# Sheet2_2.net
KiCad netlist of a schematic drawn in Altium Designer
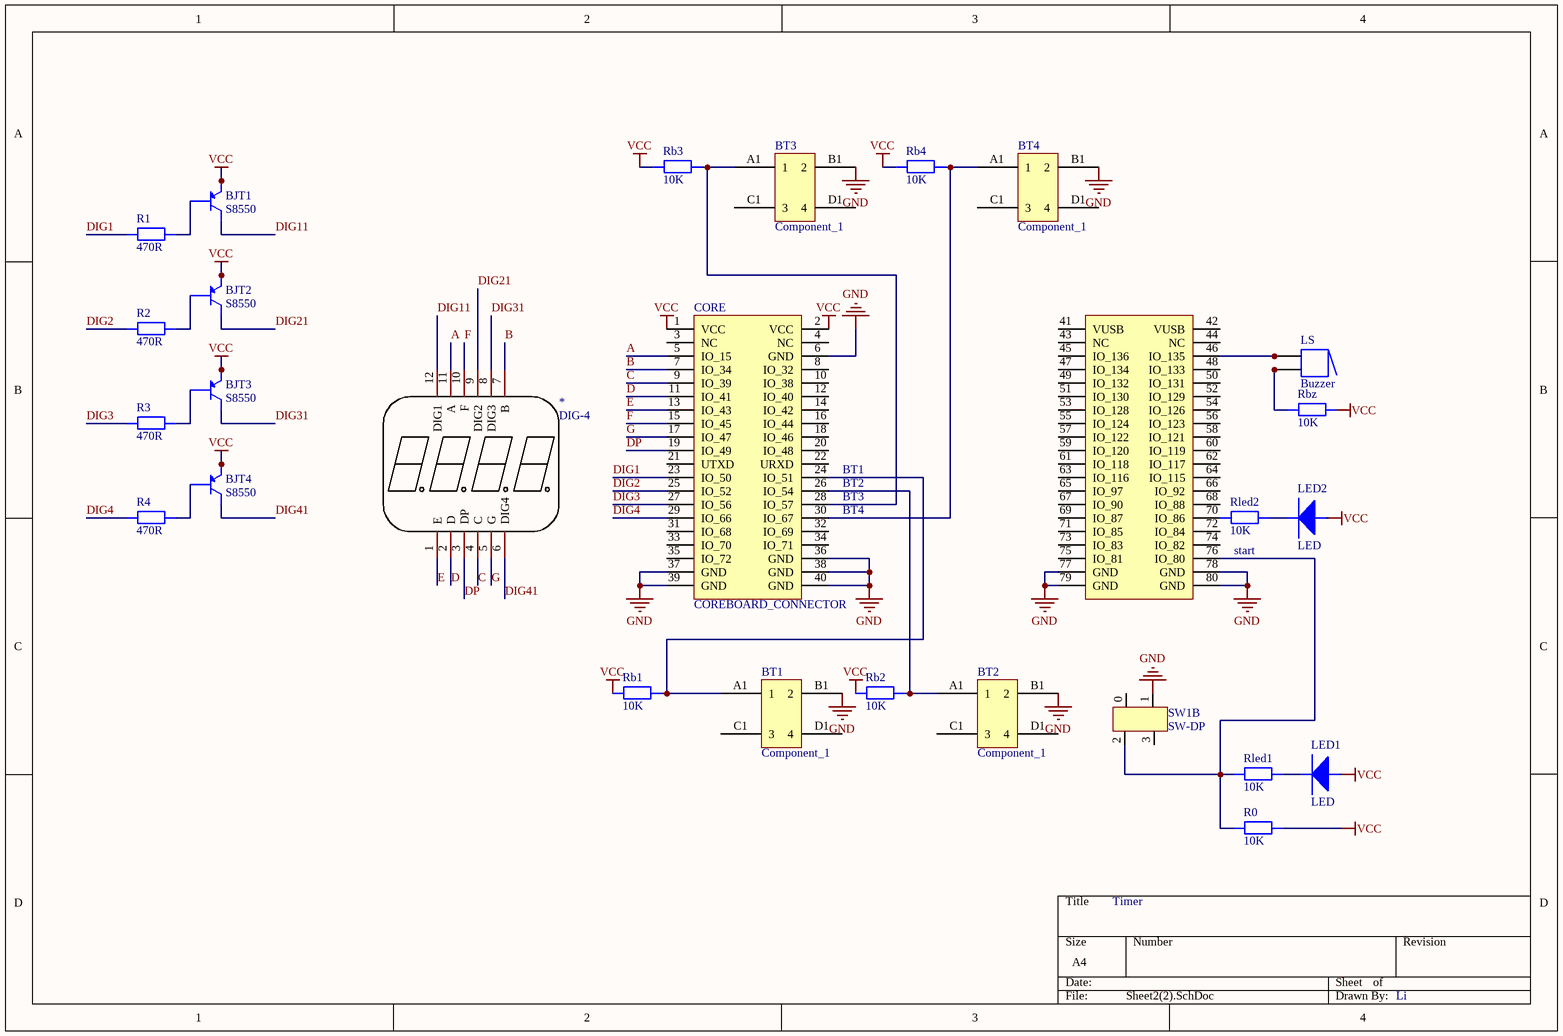
[diagram p0: Sheet2(2).SchDoc]

(export (version "E")
  (design (tool "Eeschema 10.0.6"))
  (components
    (comp (ref "*") (value "DIG-4") (footprint "DIG-4") (libsource (lib "原理图库") (part "DIG-4")))
    (comp (ref "BJT1") (value "S8550") (footprint "TO-92") (libsource (lib "Copy of 原理图库") (part "S8550")))
    (comp (ref "BJT2") (value "S8550") (footprint "TO-92") (libsource (lib "Copy of 原理图库") (part "S8550")))
    (comp (ref "BJT3") (value "S8550") (footprint "TO-92") (libsource (lib "Copy of 原理图库") (part "S8550")))
    (comp (ref "BJT4") (value "S8550") (footprint "TO-92") (libsource (lib "Copy of 原理图库") (part "S8550")))
    (comp (ref "BT1")
      (value "Component_1")
      (footprint "TS665CJ")
      (libsource (lib "Schlib1") (part "Component_1"))
    )
    (comp (ref "BT2")
      (value "Component_1")
      (footprint "TS665CJ")
      (libsource (lib "Schlib1") (part "Component_1"))
    )
    (comp (ref "BT3")
      (value "Component_1")
      (footprint "TS665CJ")
      (libsource (lib "Schlib1") (part "Component_1"))
    )
    (comp (ref "BT4")
      (value "Component_1")
      (footprint "TS665CJ")
      (libsource (lib "Schlib1") (part "Component_1"))
    )
    (comp (ref "CORE")
      (value "COREBOARD_CONNECTOR")
      (footprint "coreboard_connector")
      (libsource (lib "原理图库") (part "COREBOARD_CONNECTOR"))
    )
    (comp (ref "LED1")
      (value "LED")
      (footprint "LED_TH_HLMP4700")
      (libsource (lib "Copy of 原理图库") (part "LED"))
    )
    (comp (ref "LED2")
      (value "LED")
      (footprint "LED_TH_HLMP4700")
      (libsource (lib "Copy of 原理图库") (part "LED"))
    )
    (comp (ref "LS")
      (value "Buzzer")
      (footprint "ABSM-1574")
      (description "Magnetic Transducer Buzzer")
      (fields (field (name "PUBLISHER") "Altium Limited"))
      (libsource (lib "Miscellaneous Devices") (part "Buzzer"))
    )
    (comp (ref "R0") (value "10K") (footprint "AXIAL-0.5") (libsource (lib "Copy of 原理图库") (part "AXIAL")))
    (comp (ref "R1") (value "470R") (footprint "AXIAL-0.5") (libsource (lib "Copy of 原理图库") (part "AXIAL")))
    (comp (ref "R2") (value "470R") (footprint "AXIAL-0.5") (libsource (lib "Copy of 原理图库") (part "AXIAL")))
    (comp (ref "R3") (value "470R") (footprint "AXIAL-0.5") (libsource (lib "Copy of 原理图库") (part "AXIAL")))
    (comp (ref "R4") (value "470R") (footprint "AXIAL-0.5") (libsource (lib "Copy of 原理图库") (part "AXIAL")))
    (comp (ref "Rb1") (value "10K") (footprint "AXIAL-0.5") (libsource (lib "原理图库") (part "AXIAL")))
    (comp (ref "Rb2") (value "10K") (footprint "AXIAL-0.5") (libsource (lib "原理图库") (part "AXIAL")))
    (comp (ref "Rb3") (value "10K") (footprint "AXIAL-0.5") (libsource (lib "原理图库") (part "AXIAL")))
    (comp (ref "Rb4") (value "10K") (footprint "AXIAL-0.5") (libsource (lib "原理图库") (part "AXIAL")))
    (comp (ref "Rbz") (value "10K") (footprint "AXIAL-0.5") (libsource (lib "Copy of 原理图库") (part "AXIAL")))
    (comp (ref "Rled1") (value "10K") (footprint "AXIAL-0.5") (libsource (lib "Copy of 原理图库") (part "AXIAL")))
    (comp (ref "Rled2") (value "10K") (footprint "AXIAL-0.5") (libsource (lib "Copy of 原理图库") (part "AXIAL")))
    (comp (ref "SW1")
      (value "SW-DP")
      (footprint "SW-DP_5P_W")
      (libsource (lib "Copy of 原理图库") (part "SW-DP"))
    )
  )
  (nets
    (net (code "1") (name "/A") (class "Default")
      (node (ref "*") (pin "11") (pinfunction "A_11") (pintype "passive"))
      (node (ref "CORE") (pin "5") (pinfunction "IO_15_5") (pintype "passive"))
    )
    (net (code "2") (name "/B") (class "Default")
      (node (ref "*") (pin "7") (pinfunction "B_7") (pintype "passive"))
      (node (ref "CORE") (pin "7") (pinfunction "IO_34_7") (pintype "passive"))
    )
    (net (code "3") (name "/C") (class "Default")
      (node (ref "*") (pin "4") (pinfunction "C_4") (pintype "passive"))
      (node (ref "CORE") (pin "9") (pinfunction "IO_39_9") (pintype "passive"))
    )
    (net (code "4") (name "/D") (class "Default")
      (node (ref "*") (pin "2") (pinfunction "D_2") (pintype "passive"))
      (node (ref "CORE") (pin "11") (pinfunction "IO_41_11") (pintype "passive"))
    )
    (net (code "5") (name "/DIG1") (class "Default")
      (node (ref "CORE") (pin "23") (pinfunction "IO_50_23") (pintype "passive"))
      (node (ref "R1") (pin "1") (pinfunction "1_1") (pintype "passive"))
    )
    (net (code "6") (name "/DIG2") (class "Default")
      (node (ref "CORE") (pin "25") (pinfunction "IO_52_25") (pintype "passive"))
      (node (ref "R2") (pin "1") (pinfunction "1_1") (pintype "passive"))
    )
    (net (code "7") (name "/DIG3") (class "Default")
      (node (ref "CORE") (pin "27") (pinfunction "IO_56_27") (pintype "passive"))
      (node (ref "R3") (pin "1") (pinfunction "1_1") (pintype "passive"))
    )
    (net (code "8") (name "/DIG4") (class "Default")
      (node (ref "CORE") (pin "29") (pinfunction "IO_66_29") (pintype "passive"))
      (node (ref "R4") (pin "1") (pinfunction "1_1") (pintype "passive"))
    )
    (net (code "9") (name "/DIG11") (class "Default")
      (node (ref "*") (pin "12") (pinfunction "DIG1_12") (pintype "passive"))
      (node (ref "BJT1") (pin "3") (pinfunction "3_3") (pintype "passive"))
    )
    (net (code "10") (name "/DIG21") (class "Default")
      (node (ref "*") (pin "9") (pinfunction "DIG2_9") (pintype "passive"))
      (node (ref "BJT2") (pin "3") (pinfunction "3_3") (pintype "passive"))
    )
    (net (code "11") (name "/DIG31") (class "Default")
      (node (ref "*") (pin "8") (pinfunction "DIG3_8") (pintype "passive"))
      (node (ref "BJT3") (pin "3") (pinfunction "3_3") (pintype "passive"))
    )
    (net (code "12") (name "/DIG41") (class "Default")
      (node (ref "*") (pin "6") (pinfunction "DIG4_6") (pintype "passive"))
      (node (ref "BJT4") (pin "3") (pinfunction "3_3") (pintype "passive"))
    )
    (net (code "13") (name "/DP") (class "Default")
      (node (ref "*") (pin "3") (pinfunction "DP_3") (pintype "passive"))
      (node (ref "CORE") (pin "19") (pinfunction "IO_49_19") (pintype "passive"))
    )
    (net (code "14") (name "/E") (class "Default")
      (node (ref "*") (pin "1") (pinfunction "E_1") (pintype "passive"))
      (node (ref "CORE") (pin "13") (pinfunction "IO_43_13") (pintype "passive"))
    )
    (net (code "15") (name "/F") (class "Default")
      (node (ref "*") (pin "10") (pinfunction "F_10") (pintype "passive"))
      (node (ref "CORE") (pin "15") (pinfunction "IO_45_15") (pintype "passive"))
    )
    (net (code "16") (name "/G") (class "Default")
      (node (ref "*") (pin "5") (pinfunction "G_5") (pintype "passive"))
      (node (ref "CORE") (pin "17") (pinfunction "IO_47_17") (pintype "passive"))
    )
    (net (code "17") (name "GND") (class "Default")
      (node (ref "BT1") (pin "B1") (pinfunction "2_B1") (pintype "passive"))
      (node (ref "BT2") (pin "B1") (pinfunction "2_B1") (pintype "passive"))
      (node (ref "BT3") (pin "B1") (pinfunction "2_B1") (pintype "passive"))
      (node (ref "BT4") (pin "B1") (pinfunction "2_B1") (pintype "passive"))
      (node (ref "CORE") (pin "36") (pinfunction "GND_36") (pintype "passive"))
      (node (ref "CORE") (pin "37") (pinfunction "GND_37") (pintype "passive"))
      (node (ref "CORE") (pin "38") (pinfunction "GND_38") (pintype "passive"))
      (node (ref "CORE") (pin "39") (pinfunction "GND_39") (pintype "passive"))
      (node (ref "CORE") (pin "40") (pinfunction "GND_40") (pintype "passive"))
      (node (ref "CORE") (pin "6") (pinfunction "GND_6") (pintype "passive"))
      (node (ref "CORE") (pin "77") (pinfunction "GND_77") (pintype "passive"))
      (node (ref "CORE") (pin "78") (pinfunction "GND_78") (pintype "passive"))
      (node (ref "CORE") (pin "79") (pinfunction "GND_79") (pintype "passive"))
      (node (ref "CORE") (pin "80") (pinfunction "GND_80") (pintype "passive"))
      (node (ref "SW1") (pin "1") (pinfunction "1_1") (pintype "passive"))
    )
    (net (code "18") (name "Net-(BJT1-Pad2)") (class "Default")
      (node (ref "BJT1") (pin "2") (pinfunction "2_2") (pintype "passive"))
      (node (ref "R1") (pin "2") (pinfunction "2_2") (pintype "passive"))
    )
    (net (code "19") (name "Net-(BJT2-Pad2)") (class "Default")
      (node (ref "BJT2") (pin "2") (pinfunction "2_2") (pintype "passive"))
      (node (ref "R2") (pin "2") (pinfunction "2_2") (pintype "passive"))
    )
    (net (code "20") (name "Net-(BJT3-Pad2)") (class "Default")
      (node (ref "BJT3") (pin "2") (pinfunction "2_2") (pintype "passive"))
      (node (ref "R3") (pin "2") (pinfunction "2_2") (pintype "passive"))
    )
    (net (code "21") (name "Net-(BJT4-Pad2)") (class "Default")
      (node (ref "BJT4") (pin "2") (pinfunction "2_2") (pintype "passive"))
      (node (ref "R4") (pin "2") (pinfunction "2_2") (pintype "passive"))
    )
    (net (code "22") (name "Net-(BT1-1)") (class "Default")
      (node (ref "BT1") (pin "A1") (pinfunction "1_A1") (pintype "passive"))
      (node (ref "CORE") (pin "24") (pinfunction "IO_51_24") (pintype "passive"))
      (node (ref "Rb1") (pin "2") (pinfunction "2_2") (pintype "passive"))
    )
    (net (code "23") (name "Net-(BT2-1)") (class "Default")
      (node (ref "BT2") (pin "A1") (pinfunction "1_A1") (pintype "passive"))
      (node (ref "CORE") (pin "26") (pinfunction "IO_54_26") (pintype "passive"))
      (node (ref "Rb2") (pin "2") (pinfunction "2_2") (pintype "passive"))
    )
    (net (code "24") (name "Net-(BT3-1)") (class "Default")
      (node (ref "BT3") (pin "A1") (pinfunction "1_A1") (pintype "passive"))
      (node (ref "CORE") (pin "28") (pinfunction "IO_57_28") (pintype "passive"))
      (node (ref "Rb3") (pin "2") (pinfunction "2_2") (pintype "passive"))
    )
    (net (code "25") (name "Net-(BT4-1)") (class "Default")
      (node (ref "BT4") (pin "A1") (pinfunction "1_A1") (pintype "passive"))
      (node (ref "CORE") (pin "30") (pinfunction "IO_67_30") (pintype "passive"))
      (node (ref "Rb4") (pin "2") (pinfunction "2_2") (pintype "passive"))
    )
    (net (code "26") (name "Net-(CORE-IO_80)") (class "Default")
      (node (ref "CORE") (pin "76") (pinfunction "IO_80_76") (pintype "passive"))
      (node (ref "R0") (pin "1") (pinfunction "1_1") (pintype "passive"))
      (node (ref "Rled1") (pin "1") (pinfunction "1_1") (pintype "passive"))
      (node (ref "SW1") (pin "2") (pinfunction "2_2") (pintype "passive"))
    )
    (net (code "27") (name "Net-(CORE-IO_86)") (class "Default")
      (node (ref "CORE") (pin "70") (pinfunction "IO_86_70") (pintype "passive"))
      (node (ref "Rled2") (pin "1") (pinfunction "1_1") (pintype "passive"))
    )
    (net (code "28") (name "Net-(CORE-IO_135)") (class "Default")
      (node (ref "CORE") (pin "46") (pinfunction "IO_135_46") (pintype "passive"))
      (node (ref "LS") (pin "1") (pinfunction "1_1") (pintype "passive"))
      (node (ref "LS") (pin "1A") (pinfunction "1A_1A") (pintype "passive"))
    )
    (net (code "29") (name "Net-(LED1-Pad1)") (class "Default")
      (node (ref "LED1") (pin "1") (pinfunction "1_1") (pintype "passive"))
      (node (ref "Rled1") (pin "2") (pinfunction "2_2") (pintype "passive"))
    )
    (net (code "30") (name "Net-(LED2-Pad1)") (class "Default")
      (node (ref "LED2") (pin "1") (pinfunction "1_1") (pintype "passive"))
      (node (ref "Rled2") (pin "2") (pinfunction "2_2") (pintype "passive"))
    )
    (net (code "31") (name "Net-(LS-Pad2)") (class "Default")
      (node (ref "LS") (pin "2") (pinfunction "2_2") (pintype "passive"))
      (node (ref "LS") (pin "2A") (pinfunction "2A_2A") (pintype "passive"))
      (node (ref "Rbz") (pin "1") (pinfunction "1_1") (pintype "passive"))
    )
    (net (code "32") (name "VCC") (class "Default")
      (node (ref "BJT1") (pin "1") (pinfunction "1_1") (pintype "passive"))
      (node (ref "BJT2") (pin "1") (pinfunction "1_1") (pintype "passive"))
      (node (ref "BJT3") (pin "1") (pinfunction "1_1") (pintype "passive"))
      (node (ref "BJT4") (pin "1") (pinfunction "1_1") (pintype "passive"))
      (node (ref "CORE") (pin "1") (pinfunction "VCC_1") (pintype "passive"))
      (node (ref "CORE") (pin "2") (pinfunction "VCC_2") (pintype "passive"))
      (node (ref "LED1") (pin "2") (pinfunction "2_2") (pintype "passive"))
      (node (ref "LED2") (pin "2") (pinfunction "2_2") (pintype "passive"))
      (node (ref "R0") (pin "2") (pinfunction "2_2") (pintype "passive"))
      (node (ref "Rb1") (pin "1") (pinfunction "1_1") (pintype "passive"))
      (node (ref "Rb2") (pin "1") (pinfunction "1_1") (pintype "passive"))
      (node (ref "Rb3") (pin "1") (pinfunction "1_1") (pintype "passive"))
      (node (ref "Rb4") (pin "1") (pinfunction "1_1") (pintype "passive"))
      (node (ref "Rbz") (pin "2") (pinfunction "2_2") (pintype "passive"))
    )
    (net (code "33") (name "unconnected-(BT1-3-PadC1)") (class "Default")
      (node (ref "BT1") (pin "C1") (pinfunction "3_C1") (pintype "passive"))
    )
    (net (code "34") (name "unconnected-(BT1-4-PadD1)") (class "Default")
      (node (ref "BT1") (pin "D1") (pinfunction "4_D1") (pintype "passive"))
    )
    (net (code "35") (name "unconnected-(BT2-3-PadC1)") (class "Default")
      (node (ref "BT2") (pin "C1") (pinfunction "3_C1") (pintype "passive"))
    )
    (net (code "36") (name "unconnected-(BT2-4-PadD1)") (class "Default")
      (node (ref "BT2") (pin "D1") (pinfunction "4_D1") (pintype "passive"))
    )
    (net (code "37") (name "unconnected-(BT3-3-PadC1)") (class "Default")
      (node (ref "BT3") (pin "C1") (pinfunction "3_C1") (pintype "passive"))
    )
    (net (code "38") (name "unconnected-(BT3-4-PadD1)") (class "Default")
      (node (ref "BT3") (pin "D1") (pinfunction "4_D1") (pintype "passive"))
    )
    (net (code "39") (name "unconnected-(BT4-3-PadC1)") (class "Default")
      (node (ref "BT4") (pin "C1") (pinfunction "3_C1") (pintype "passive"))
    )
    (net (code "40") (name "unconnected-(BT4-4-PadD1)") (class "Default")
      (node (ref "BT4") (pin "D1") (pinfunction "4_D1") (pintype "passive"))
    )
    (net (code "41") (name "unconnected-(CORE-IO_32-Pad8)") (class "Default")
      (node (ref "CORE") (pin "8") (pinfunction "IO_32_8") (pintype "passive"))
    )
    (net (code "42") (name "unconnected-(CORE-IO_38-Pad10)") (class "Default")
      (node (ref "CORE") (pin "10") (pinfunction "IO_38_10") (pintype "passive"))
    )
    (net (code "43") (name "unconnected-(CORE-IO_40-Pad12)") (class "Default")
      (node (ref "CORE") (pin "12") (pinfunction "IO_40_12") (pintype "passive"))
    )
    (net (code "44") (name "unconnected-(CORE-IO_42-Pad14)") (class "Default")
      (node (ref "CORE") (pin "14") (pinfunction "IO_42_14") (pintype "passive"))
    )
    (net (code "45") (name "unconnected-(CORE-IO_44-Pad16)") (class "Default")
      (node (ref "CORE") (pin "16") (pinfunction "IO_44_16") (pintype "passive"))
    )
    (net (code "46") (name "unconnected-(CORE-IO_46-Pad18)") (class "Default")
      (node (ref "CORE") (pin "18") (pinfunction "IO_46_18") (pintype "passive"))
    )
    (net (code "47") (name "unconnected-(CORE-IO_48-Pad20)") (class "Default")
      (node (ref "CORE") (pin "20") (pinfunction "IO_48_20") (pintype "passive"))
    )
    (net (code "48") (name "unconnected-(CORE-IO_68-Pad31)") (class "Default")
      (node (ref "CORE") (pin "31") (pinfunction "IO_68_31") (pintype "passive"))
    )
    (net (code "49") (name "unconnected-(CORE-IO_69-Pad32)") (class "Default")
      (node (ref "CORE") (pin "32") (pinfunction "IO_69_32") (pintype "passive"))
    )
    (net (code "50") (name "unconnected-(CORE-IO_70-Pad33)") (class "Default")
      (node (ref "CORE") (pin "33") (pinfunction "IO_70_33") (pintype "passive"))
    )
    (net (code "51") (name "unconnected-(CORE-IO_71-Pad34)") (class "Default")
      (node (ref "CORE") (pin "34") (pinfunction "IO_71_34") (pintype "passive"))
    )
    (net (code "52") (name "unconnected-(CORE-IO_72-Pad35)") (class "Default")
      (node (ref "CORE") (pin "35") (pinfunction "IO_72_35") (pintype "passive"))
    )
    (net (code "53") (name "unconnected-(CORE-IO_81-Pad75)") (class "Default")
      (node (ref "CORE") (pin "75") (pinfunction "IO_81_75") (pintype "passive"))
    )
    (net (code "54") (name "unconnected-(CORE-IO_82-Pad74)") (class "Default")
      (node (ref "CORE") (pin "74") (pinfunction "IO_82_74") (pintype "passive"))
    )
    (net (code "55") (name "unconnected-(CORE-IO_83-Pad73)") (class "Default")
      (node (ref "CORE") (pin "73") (pinfunction "IO_83_73") (pintype "passive"))
    )
    (net (code "56") (name "unconnected-(CORE-IO_84-Pad72)") (class "Default")
      (node (ref "CORE") (pin "72") (pinfunction "IO_84_72") (pintype "passive"))
    )
    (net (code "57") (name "unconnected-(CORE-IO_85-Pad71)") (class "Default")
      (node (ref "CORE") (pin "71") (pinfunction "IO_85_71") (pintype "passive"))
    )
    (net (code "58") (name "unconnected-(CORE-IO_87-Pad69)") (class "Default")
      (node (ref "CORE") (pin "69") (pinfunction "IO_87_69") (pintype "passive"))
    )
    (net (code "59") (name "unconnected-(CORE-IO_88-Pad68)") (class "Default")
      (node (ref "CORE") (pin "68") (pinfunction "IO_88_68") (pintype "passive"))
    )
    (net (code "60") (name "unconnected-(CORE-IO_90-Pad67)") (class "Default")
      (node (ref "CORE") (pin "67") (pinfunction "IO_90_67") (pintype "passive"))
    )
    (net (code "61") (name "unconnected-(CORE-IO_92-Pad66)") (class "Default")
      (node (ref "CORE") (pin "66") (pinfunction "IO_92_66") (pintype "passive"))
    )
    (net (code "62") (name "unconnected-(CORE-IO_97-Pad65)") (class "Default")
      (node (ref "CORE") (pin "65") (pinfunction "IO_97_65") (pintype "passive"))
    )
    (net (code "63") (name "unconnected-(CORE-IO_115-Pad64)") (class "Default")
      (node (ref "CORE") (pin "64") (pinfunction "IO_115_64") (pintype "passive"))
    )
    (net (code "64") (name "unconnected-(CORE-IO_116-Pad63)") (class "Default")
      (node (ref "CORE") (pin "63") (pinfunction "IO_116_63") (pintype "passive"))
    )
    (net (code "65") (name "unconnected-(CORE-IO_117-Pad62)") (class "Default")
      (node (ref "CORE") (pin "62") (pinfunction "IO_117_62") (pintype "passive"))
    )
    (net (code "66") (name "unconnected-(CORE-IO_118-Pad61)") (class "Default")
      (node (ref "CORE") (pin "61") (pinfunction "IO_118_61") (pintype "passive"))
    )
    (net (code "67") (name "unconnected-(CORE-IO_119-Pad60)") (class "Default")
      (node (ref "CORE") (pin "60") (pinfunction "IO_119_60") (pintype "passive"))
    )
    (net (code "68") (name "unconnected-(CORE-IO_120-Pad59)") (class "Default")
      (node (ref "CORE") (pin "59") (pinfunction "IO_120_59") (pintype "passive"))
    )
    (net (code "69") (name "unconnected-(CORE-IO_121-Pad58)") (class "Default")
      (node (ref "CORE") (pin "58") (pinfunction "IO_121_58") (pintype "passive"))
    )
    (net (code "70") (name "unconnected-(CORE-IO_122-Pad57)") (class "Default")
      (node (ref "CORE") (pin "57") (pinfunction "IO_122_57") (pintype "passive"))
    )
    (net (code "71") (name "unconnected-(CORE-IO_123-Pad56)") (class "Default")
      (node (ref "CORE") (pin "56") (pinfunction "IO_123_56") (pintype "passive"))
    )
    (net (code "72") (name "unconnected-(CORE-IO_124-Pad55)") (class "Default")
      (node (ref "CORE") (pin "55") (pinfunction "IO_124_55") (pintype "passive"))
    )
    (net (code "73") (name "unconnected-(CORE-IO_126-Pad54)") (class "Default")
      (node (ref "CORE") (pin "54") (pinfunction "IO_126_54") (pintype "passive"))
    )
    (net (code "74") (name "unconnected-(CORE-IO_128-Pad53)") (class "Default")
      (node (ref "CORE") (pin "53") (pinfunction "IO_128_53") (pintype "passive"))
    )
    (net (code "75") (name "unconnected-(CORE-IO_129-Pad52)") (class "Default")
      (node (ref "CORE") (pin "52") (pinfunction "IO_129_52") (pintype "passive"))
    )
    (net (code "76") (name "unconnected-(CORE-IO_130-Pad51)") (class "Default")
      (node (ref "CORE") (pin "51") (pinfunction "IO_130_51") (pintype "passive"))
    )
    (net (code "77") (name "unconnected-(CORE-IO_131-Pad50)") (class "Default")
      (node (ref "CORE") (pin "50") (pinfunction "IO_131_50") (pintype "passive"))
    )
    (net (code "78") (name "unconnected-(CORE-IO_132-Pad49)") (class "Default")
      (node (ref "CORE") (pin "49") (pinfunction "IO_132_49") (pintype "passive"))
    )
    (net (code "79") (name "unconnected-(CORE-IO_133-Pad48)") (class "Default")
      (node (ref "CORE") (pin "48") (pinfunction "IO_133_48") (pintype "passive"))
    )
    (net (code "80") (name "unconnected-(CORE-IO_134-Pad47)") (class "Default")
      (node (ref "CORE") (pin "47") (pinfunction "IO_134_47") (pintype "passive"))
    )
    (net (code "81") (name "unconnected-(CORE-IO_136-Pad45)") (class "Default")
      (node (ref "CORE") (pin "45") (pinfunction "IO_136_45") (pintype "passive"))
    )
    (net (code "82") (name "unconnected-(CORE-NC-Pad3)") (class "Default")
      (node (ref "CORE") (pin "3") (pinfunction "NC_3") (pintype "passive"))
    )
    (net (code "83") (name "unconnected-(CORE-NC-Pad4)") (class "Default")
      (node (ref "CORE") (pin "4") (pinfunction "NC_4") (pintype "passive"))
    )
    (net (code "84") (name "unconnected-(CORE-NC-Pad43)") (class "Default")
      (node (ref "CORE") (pin "43") (pinfunction "NC_43") (pintype "passive"))
    )
    (net (code "85") (name "unconnected-(CORE-NC-Pad44)") (class "Default")
      (node (ref "CORE") (pin "44") (pinfunction "NC_44") (pintype "passive"))
    )
    (net (code "86") (name "unconnected-(CORE-URXD-Pad22)") (class "Default")
      (node (ref "CORE") (pin "22") (pinfunction "URXD_22") (pintype "passive"))
    )
    (net (code "87") (name "unconnected-(CORE-UTXD-Pad21)") (class "Default")
      (node (ref "CORE") (pin "21") (pinfunction "UTXD_21") (pintype "passive"))
    )
    (net (code "88") (name "unconnected-(CORE-VUSB-Pad41)") (class "Default")
      (node (ref "CORE") (pin "41") (pinfunction "VUSB_41") (pintype "passive"))
    )
    (net (code "89") (name "unconnected-(CORE-VUSB-Pad42)") (class "Default")
      (node (ref "CORE") (pin "42") (pinfunction "VUSB_42") (pintype "passive"))
    )
    (net (code "90") (name "unconnected-(SW1-Pad0)") (class "Default")
      (node (ref "SW1") (pin "0") (pinfunction "0_0") (pintype "passive"))
    )
    (net (code "91") (name "unconnected-(SW1-Pad3)") (class "Default")
      (node (ref "SW1") (pin "3") (pinfunction "3_3") (pintype "passive"))
    )
  )
)
